# Channel_2.net
KiCad netlist of a schematic drawn in Altium Designer
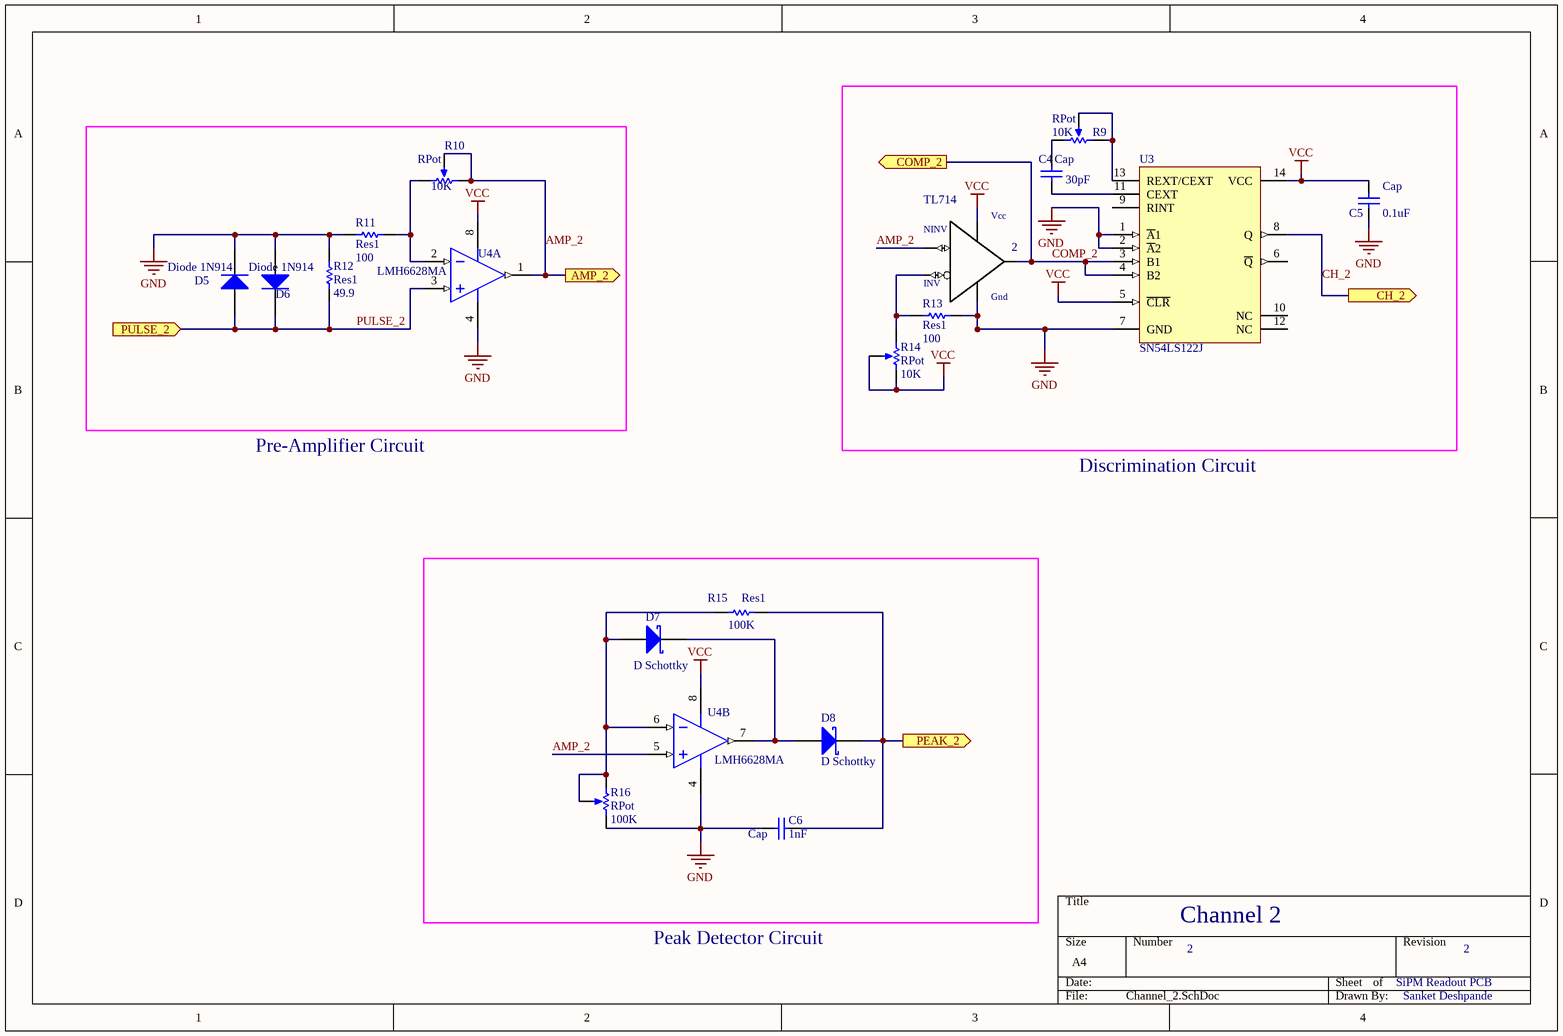
[diagram p0: Channel_2.SchDoc]

(export (version "E")
  (design (tool "Eeschema 10.0.6"))
  (components
    (comp (ref "2")
      (value "TL714")
      (footprint "SO-08M")
      (fields (field (name "MF") "Texas Instruments"))
      (libsource (lib "TL714") (part "TL714"))
    )
    (comp (ref "C4")
      (value "Cap")
      (footprint "RAD-0.3")
      (description "Capacitor")
      (fields (field (name "ALTIUM_VALUE") "30pF") (field (name "PUBLISHER") "Altium Limited"))
      (libsource (lib "Miscellaneous Devices") (part "Cap"))
    )
    (comp (ref "C5")
      (value "Cap")
      (footprint "RAD-0.3")
      (description "Capacitor")
      (fields (field (name "ALTIUM_VALUE") "0.1uF") (field (name "PUBLISHER") "Altium Limited"))
      (libsource (lib "Miscellaneous Devices") (part "Cap"))
    )
    (comp (ref "C6")
      (value "Cap")
      (footprint "RAD-0.3")
      (description "Capacitor")
      (fields (field (name "ALTIUM_VALUE") "1nF") (field (name "PUBLISHER") "Altium Limited"))
      (libsource (lib "Miscellaneous Devices") (part "Cap"))
    )
    (comp (ref "D5")
      (value "Diode 1N914")
      (footprint "DO-35")
      (description "High Conductance Fast Diode")
      (fields (field (name "PUBLISHER") "Altium Limited"))
      (libsource (lib "Miscellaneous Devices") (part "Diode 1N914"))
    )
    (comp (ref "D6")
      (value "Diode 1N914")
      (footprint "DO-35")
      (description "High Conductance Fast Diode")
      (fields (field (name "PUBLISHER") "Altium Limited"))
      (libsource (lib "Miscellaneous Devices") (part "Diode 1N914"))
    )
    (comp (ref "D7")
      (value "D Schottky")
      (footprint "SMB")
      (description "Schottky Diode")
      (fields (field (name "PUBLISHER") "Altium Limited"))
      (libsource (lib "Miscellaneous Devices") (part "D Schottky"))
    )
    (comp (ref "D8")
      (value "D Schottky")
      (footprint "SMB")
      (description "Schottky Diode")
      (fields (field (name "PUBLISHER") "Altium Limited"))
      (libsource (lib "Miscellaneous Devices") (part "D Schottky"))
    )
    (comp (ref "R9")
      (value "RPot")
      (footprint "VR5")
      (description "Potentiometer")
      (fields (field (name "ALTIUM_VALUE") "10K") (field (name "PUBLISHER") "Altium Limited"))
      (libsource (lib "Miscellaneous Devices") (part "RPot"))
    )
    (comp (ref "R10")
      (value "RPot")
      (footprint "VR5")
      (description "Potentiometer")
      (fields (field (name "ALTIUM_VALUE") "10K") (field (name "PUBLISHER") "Altium Limited"))
      (libsource (lib "Miscellaneous Devices") (part "RPot"))
    )
    (comp (ref "R11")
      (value "Res1")
      (footprint "AXIAL-0.3")
      (description "Resistor")
      (fields (field (name "ALTIUM_VALUE") "100") (field (name "PUBLISHER") "Altium Limited"))
      (libsource (lib "Miscellaneous Devices") (part "Res1"))
    )
    (comp (ref "R12")
      (value "Res1")
      (footprint "AXIAL-0.3")
      (description "Resistor")
      (fields (field (name "ALTIUM_VALUE") "49.9") (field (name "PUBLISHER") "Altium Limited"))
      (libsource (lib "Miscellaneous Devices") (part "Res1"))
    )
    (comp (ref "R13")
      (value "Res1")
      (footprint "AXIAL-0.3")
      (description "Resistor")
      (fields (field (name "ALTIUM_VALUE") "100") (field (name "PUBLISHER") "Altium Limited"))
      (libsource (lib "Miscellaneous Devices") (part "Res1"))
    )
    (comp (ref "R14")
      (value "RPot")
      (footprint "VR5")
      (description "Potentiometer")
      (fields (field (name "ALTIUM_VALUE") "10K") (field (name "PUBLISHER") "Altium Limited"))
      (libsource (lib "Miscellaneous Devices") (part "RPot"))
    )
    (comp (ref "R15")
      (value "Res1")
      (footprint "AXIAL-0.3")
      (description "Resistor")
      (fields (field (name "ALTIUM_VALUE") "100K") (field (name "PUBLISHER") "Altium Limited"))
      (libsource (lib "Miscellaneous Devices") (part "Res1"))
    )
    (comp (ref "R16")
      (value "RPot")
      (footprint "VR5")
      (description "Potentiometer")
      (fields (field (name "ALTIUM_VALUE") "100K") (field (name "PUBLISHER") "Altium Limited"))
      (libsource (lib "Miscellaneous Devices") (part "RPot"))
    )
    (comp (ref "U3")
      (value "SN54LS122J")
      (footprint "J014")
      (description "Retriggerable Monostable Multivibrator")
      (fields (field (name "PUBLISHER") "Altium Limited"))
      (libsource (lib "TI Logic Multivibrator") (part "SN54LS122J"))
    )
    (comp (ref "U4")
      (value "LMH6628MA")
      (footprint "M08A_N")
      (description "Dual Wideband, Low Noise, Voltage Feedback Op Amp, 8-pin Narrow SOIC")
      (fields (field (name "MANUFACTURER") "National Semiconductor"))
      (libsource (lib "National Semiconductor Amplifier") (part "LMH6628MA"))
    )
  )
  (nets
    (net (code "1") (name "/AMP_2") (class "Default")
      (node (ref "2") (pin "3") (pinfunction "NINV_3") (pintype "bidirectional"))
      (node (ref "R10") (pin "1") (pinfunction "TOP_1") (pintype "passive"))
      (node (ref "R10") (pin "3") (pinfunction "TAP_3") (pintype "passive"))
      (node (ref "U4") (pin "1") (pinfunction "OUT1_1") (pintype "output"))
      (node (ref "U4") (pin "5") (pinfunction "IN2+_5") (pintype "input"))
    )
    (net (code "2") (name "/CH_2") (class "Default")
      (node (ref "U3") (pin "8") (pinfunction "Q_8") (pintype "output"))
    )
    (net (code "3") (name "/COMP_2") (class "Default")
      (node (ref "2") (pin "6") (pinfunction "OUT_6") (pintype "bidirectional"))
      (node (ref "U3") (pin "3") (pinfunction "B1_3") (pintype "input"))
      (node (ref "U3") (pin "4") (pinfunction "B2_4") (pintype "input"))
    )
    (net (code "4") (name "/PEAK_2") (class "Default")
      (node (ref "C6") (pin "2") (pinfunction "2_2") (pintype "passive"))
      (node (ref "D8") (pin "2") (pinfunction "K_2") (pintype "passive"))
      (node (ref "R15") (pin "2") (pinfunction "2_2") (pintype "passive"))
    )
    (net (code "5") (name "/PULSE_2") (class "Default")
      (node (ref "D5") (pin "1") (pinfunction "A_1") (pintype "passive"))
      (node (ref "D6") (pin "2") (pinfunction "K_2") (pintype "passive"))
      (node (ref "R12") (pin "2") (pinfunction "2_2") (pintype "passive"))
      (node (ref "U4") (pin "3") (pinfunction "IN1+_3") (pintype "input"))
    )
    (net (code "6") (name "GND") (class "Default")
      (node (ref "2") (pin "5") (pinfunction "VNEG_5") (pintype "bidirectional"))
      (node (ref "C5") (pin "1") (pinfunction "1_1") (pintype "passive"))
      (node (ref "C6") (pin "1") (pinfunction "1_1") (pintype "passive"))
      (node (ref "D5") (pin "2") (pinfunction "K_2") (pintype "passive"))
      (node (ref "D6") (pin "1") (pinfunction "A_1") (pintype "passive"))
      (node (ref "R11") (pin "1") (pinfunction "1_1") (pintype "passive"))
      (node (ref "R12") (pin "1") (pinfunction "1_1") (pintype "passive"))
      (node (ref "R13") (pin "2") (pinfunction "2_2") (pintype "passive"))
      (node (ref "R16") (pin "2") (pinfunction "BOT_2") (pintype "passive"))
      (node (ref "U3") (pin "1") (pinfunction "~{A}1_1") (pintype "input"))
      (node (ref "U3") (pin "2") (pinfunction "~{A}2_2") (pintype "input"))
      (node (ref "U3") (pin "7") (pinfunction "GND_7") (pintype "power_in"))
      (node (ref "U4") (pin "4") (pinfunction "V-_4") (pintype "power_in"))
    )
    (net (code "7") (name "Net-(2-INV)") (class "Default")
      (node (ref "2") (pin "2") (pinfunction "INV_2") (pintype "bidirectional"))
      (node (ref "R13") (pin "1") (pinfunction "1_1") (pintype "passive"))
      (node (ref "R14") (pin "1") (pinfunction "TOP_1") (pintype "passive"))
    )
    (net (code "8") (name "Net-(D7-A)") (class "Default")
      (node (ref "D7") (pin "1") (pinfunction "A_1") (pintype "passive"))
      (node (ref "R15") (pin "1") (pinfunction "1_1") (pintype "passive"))
      (node (ref "R16") (pin "1") (pinfunction "TOP_1") (pintype "passive"))
      (node (ref "R16") (pin "3") (pinfunction "TAP_3") (pintype "passive"))
      (node (ref "U4") (pin "6") (pinfunction "IN2-_6") (pintype "input"))
    )
    (net (code "9") (name "Net-(D7-K)") (class "Default")
      (node (ref "D7") (pin "2") (pinfunction "K_2") (pintype "passive"))
      (node (ref "D8") (pin "1") (pinfunction "A_1") (pintype "passive"))
      (node (ref "U4") (pin "7") (pinfunction "OUT2_7") (pintype "output"))
    )
    (net (code "10") (name "Net-(R9-BOT)") (class "Default")
      (node (ref "C4") (pin "2") (pinfunction "2_2") (pintype "passive"))
      (node (ref "R9") (pin "2") (pinfunction "BOT_2") (pintype "passive"))
    )
    (net (code "11") (name "Net-(R9-TAP)") (class "Default")
      (node (ref "R9") (pin "1") (pinfunction "TOP_1") (pintype "passive"))
      (node (ref "R9") (pin "3") (pinfunction "TAP_3") (pintype "passive"))
      (node (ref "U3") (pin "13") (pinfunction "REXT/CEXT_13") (pintype "passive"))
    )
    (net (code "12") (name "Net-(R10-BOT)") (class "Default")
      (node (ref "R10") (pin "2") (pinfunction "BOT_2") (pintype "passive"))
      (node (ref "R11") (pin "2") (pinfunction "2_2") (pintype "passive"))
      (node (ref "U4") (pin "2") (pinfunction "IN1-_2") (pintype "input"))
    )
    (net (code "13") (name "Net-(U3-CEXT)") (class "Default")
      (node (ref "C4") (pin "1") (pinfunction "1_1") (pintype "passive"))
      (node (ref "U3") (pin "11") (pinfunction "CEXT_11") (pintype "passive"))
    )
    (net (code "14") (name "VCC") (class "Default")
      (node (ref "2") (pin "8") (pinfunction "VPOS_8") (pintype "bidirectional"))
      (node (ref "C5") (pin "2") (pinfunction "2_2") (pintype "passive"))
      (node (ref "R14") (pin "2") (pinfunction "BOT_2") (pintype "passive"))
      (node (ref "R14") (pin "3") (pinfunction "TAP_3") (pintype "passive"))
      (node (ref "U3") (pin "14") (pinfunction "VCC_14") (pintype "power_in"))
      (node (ref "U3") (pin "5") (pinfunction "~{CLR}_5") (pintype "input"))
      (node (ref "U4") (pin "8") (pinfunction "V+_8") (pintype "power_in"))
    )
    (net (code "15") (name "unconnected-(U3-NC-Pad10)") (class "Default")
      (node (ref "U3") (pin "10") (pinfunction "NC_10") (pintype "passive"))
    )
    (net (code "16") (name "unconnected-(U3-NC-Pad12)") (class "Default")
      (node (ref "U3") (pin "12") (pinfunction "NC_12") (pintype "passive"))
    )
    (net (code "17") (name "unconnected-(U3-RINT-Pad9)") (class "Default")
      (node (ref "U3") (pin "9") (pinfunction "RINT_9") (pintype "passive"))
    )
    (net (code "18") (name "unconnected-(U3-~{Q}-Pad6)") (class "Default")
      (node (ref "U3") (pin "6") (pinfunction "~{Q}_6") (pintype "output"))
    )
  )
)
